# MCP9808.net
KiCad netlist of a schematic drawn in EAGLE
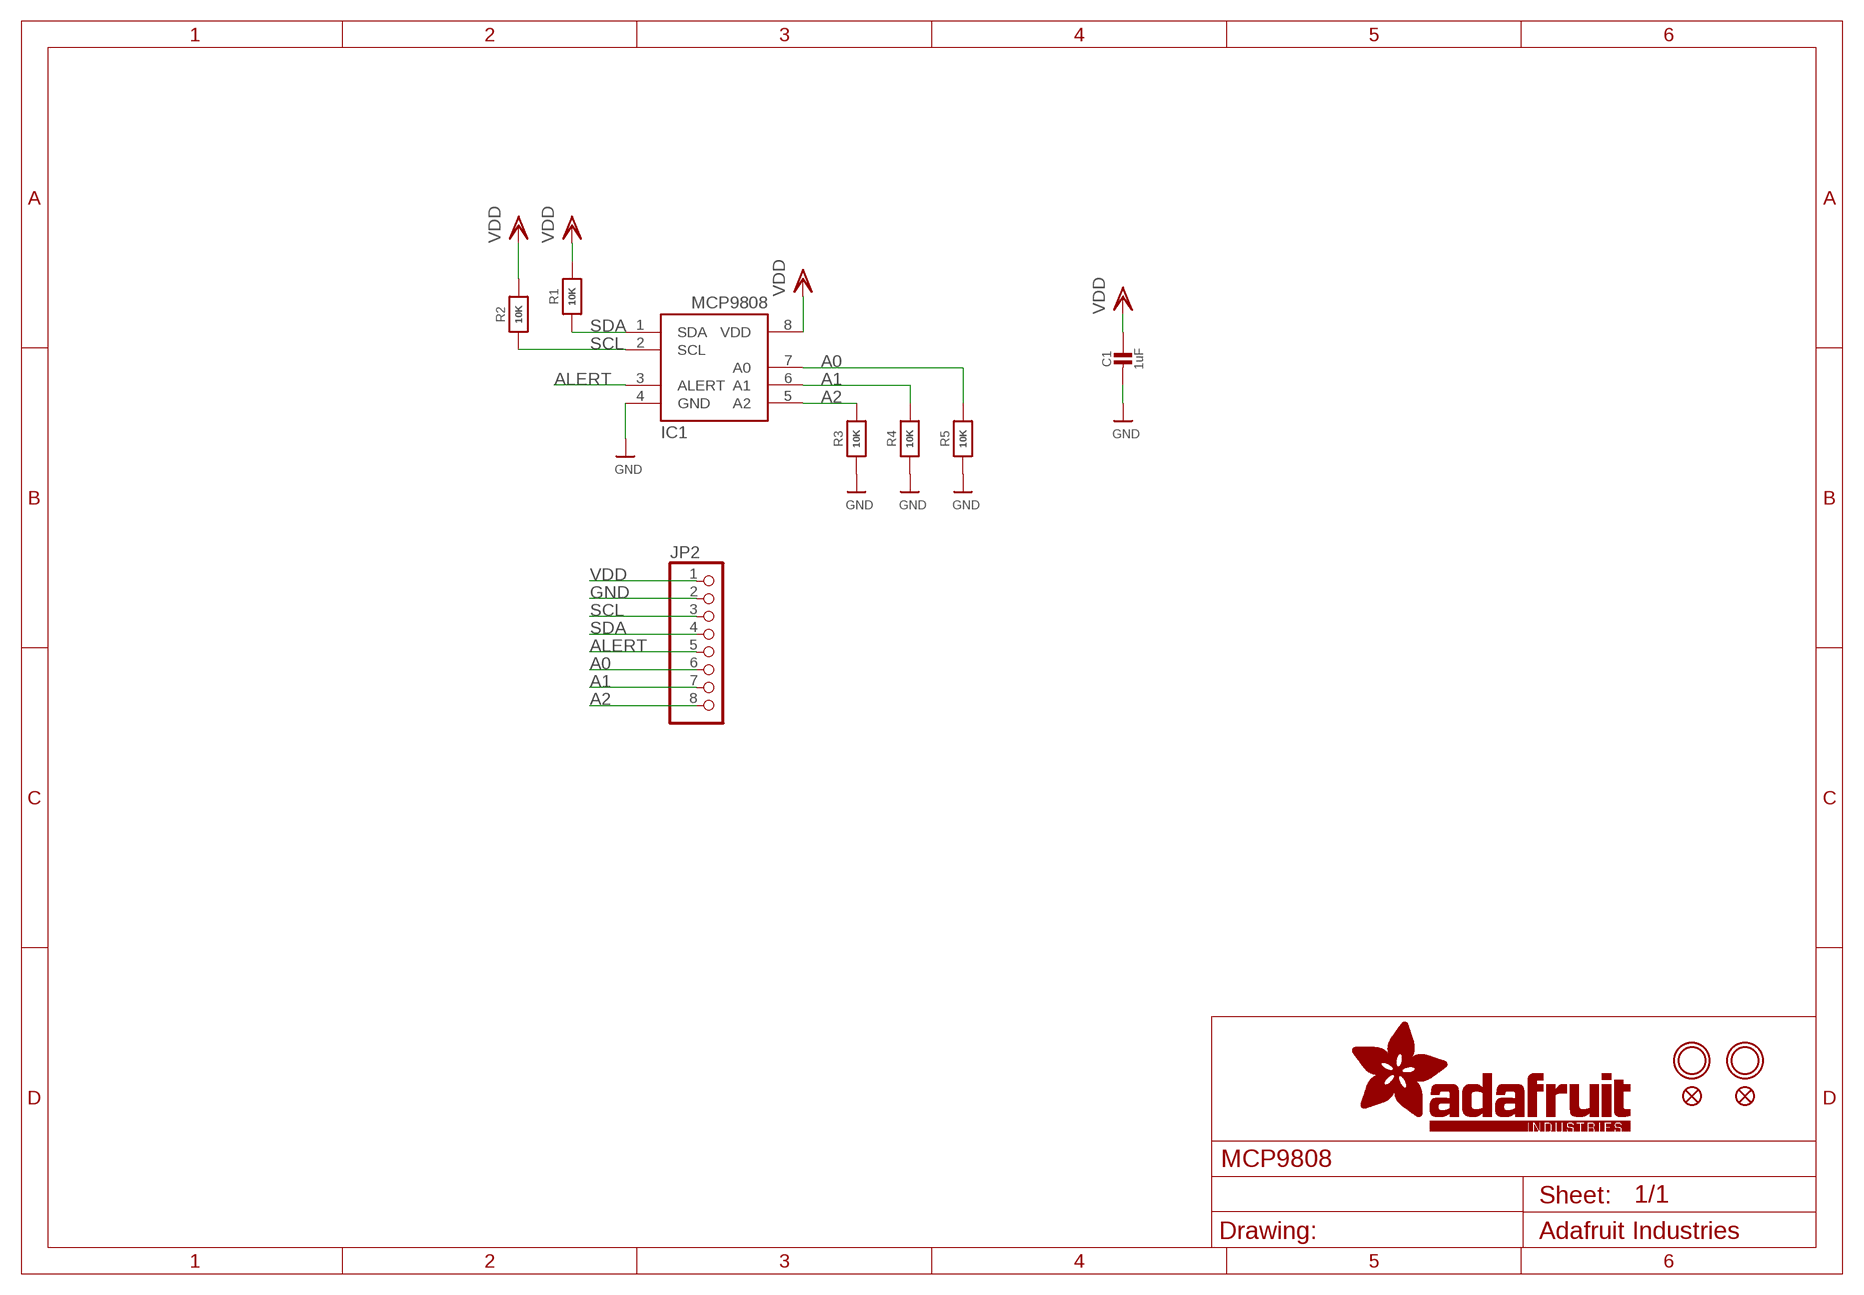
[diagram p0: schematic, sheet 1]

(export (version "E")
  (design (tool "Eeschema 10.0.6"))
  (components
    (comp (ref "C1")
      (value "1uF")
      (footprint "eagle-import:_0805MP")
      (libsource (lib "eagle-import") (part "CAP_CERAMIC_0805MP"))
    )
    (comp (ref "FID1")
      (value "FIDUCIAL\"\"")
      (footprint "eagle-import:FIDUCIAL_1MM")
      (libsource (lib "eagle-import") (part "FIDUCIAL{dblquote}{dblquote}"))
    )
    (comp (ref "FID2")
      (value "FIDUCIAL\"\"")
      (footprint "eagle-import:FIDUCIAL_1MM")
      (libsource (lib "eagle-import") (part "FIDUCIAL{dblquote}{dblquote}"))
    )
    (comp (ref "IC1")
      (value "MCP9808-E/MS")
      (footprint "eagle-import:MSOP8_0.65MM")
      (libsource (lib "eagle-import") (part "MCP9808-E/MS"))
    )
    (comp (ref "JP2")
      (value "HEADER-1X870MIL")
      (footprint "eagle-import:1X08_ROUND_70")
      (libsource (lib "eagle-import") (part "HEADER-1X870MIL"))
    )
    (comp (ref "R1")
      (value "10K")
      (footprint "eagle-import:0805-NO")
      (libsource (lib "eagle-import") (part "RESISTOR0805_NOOUTLINE"))
    )
    (comp (ref "R2")
      (value "10K")
      (footprint "eagle-import:0805-NO")
      (libsource (lib "eagle-import") (part "RESISTOR0805_NOOUTLINE"))
    )
    (comp (ref "R3")
      (value "10K")
      (footprint "eagle-import:0805-NO")
      (libsource (lib "eagle-import") (part "RESISTOR0805_NOOUTLINE"))
    )
    (comp (ref "R4")
      (value "10K")
      (footprint "eagle-import:0805-NO")
      (libsource (lib "eagle-import") (part "RESISTOR0805_NOOUTLINE"))
    )
    (comp (ref "R5")
      (value "10K")
      (footprint "eagle-import:0805-NO")
      (libsource (lib "eagle-import") (part "RESISTOR0805_NOOUTLINE"))
    )
    (comp (ref "U$3")
      (value "MOUNTINGHOLE2.5")
      (footprint "eagle-import:MOUNTINGHOLE_2.5_PLATED")
      (libsource (lib "eagle-import") (part "MOUNTINGHOLE2.5"))
    )
    (comp (ref "U$5")
      (value "MOUNTINGHOLE2.5")
      (footprint "eagle-import:MOUNTINGHOLE_2.5_PLATED")
      (libsource (lib "eagle-import") (part "MOUNTINGHOLE2.5"))
    )
  )
  (nets
    (net (code "1") (name "/A0") (class "Default")
      (node (ref "IC1") (pin "7") (pinfunction "A0_7") (pintype "input"))
      (node (ref "JP2") (pin "6") (pinfunction "6_6") (pintype "passive"))
      (node (ref "R5") (pin "2") (pinfunction "2_2") (pintype "passive"))
    )
    (net (code "2") (name "/A1") (class "Default")
      (node (ref "IC1") (pin "6") (pinfunction "A1_6") (pintype "input"))
      (node (ref "JP2") (pin "7") (pinfunction "7_7") (pintype "passive"))
      (node (ref "R4") (pin "2") (pinfunction "2_2") (pintype "passive"))
    )
    (net (code "3") (name "/A2") (class "Default")
      (node (ref "IC1") (pin "5") (pinfunction "A2_5") (pintype "input"))
      (node (ref "JP2") (pin "8") (pinfunction "8_8") (pintype "passive"))
      (node (ref "R3") (pin "2") (pinfunction "2_2") (pintype "passive"))
    )
    (net (code "4") (name "/ALERT") (class "Default")
      (node (ref "IC1") (pin "3") (pinfunction "ALERT_3") (pintype "open_collector"))
      (node (ref "JP2") (pin "5") (pinfunction "5_5") (pintype "passive"))
    )
    (net (code "5") (name "/SCL") (class "Default")
      (node (ref "IC1") (pin "2") (pinfunction "SCL_2") (pintype "bidirectional"))
      (node (ref "JP2") (pin "3") (pinfunction "3_3") (pintype "passive"))
      (node (ref "R2") (pin "1") (pinfunction "1_1") (pintype "passive"))
    )
    (net (code "6") (name "/SDA") (class "Default")
      (node (ref "IC1") (pin "1") (pinfunction "SDA_1") (pintype "bidirectional"))
      (node (ref "JP2") (pin "4") (pinfunction "4_4") (pintype "passive"))
      (node (ref "R1") (pin "1") (pinfunction "1_1") (pintype "passive"))
    )
    (net (code "7") (name "GND") (class "Default")
      (node (ref "C1") (pin "2") (pinfunction "2_2") (pintype "passive"))
      (node (ref "IC1") (pin "4") (pinfunction "GND_4") (pintype "power_in"))
      (node (ref "JP2") (pin "2") (pinfunction "2_2") (pintype "passive"))
      (node (ref "R3") (pin "1") (pinfunction "1_1") (pintype "passive"))
      (node (ref "R4") (pin "1") (pinfunction "1_1") (pintype "passive"))
      (node (ref "R5") (pin "1") (pinfunction "1_1") (pintype "passive"))
    )
    (net (code "8") (name "VDD") (class "Default")
      (node (ref "C1") (pin "1") (pinfunction "1_1") (pintype "passive"))
      (node (ref "IC1") (pin "8") (pinfunction "VDD_8") (pintype "power_in"))
      (node (ref "JP2") (pin "1") (pinfunction "1_1") (pintype "passive"))
      (node (ref "R1") (pin "2") (pinfunction "2_2") (pintype "passive"))
      (node (ref "R2") (pin "2") (pinfunction "2_2") (pintype "passive"))
    )
  )
)
